# usbspk.net
KiCad netlist of a schematic drawn in EAGLE
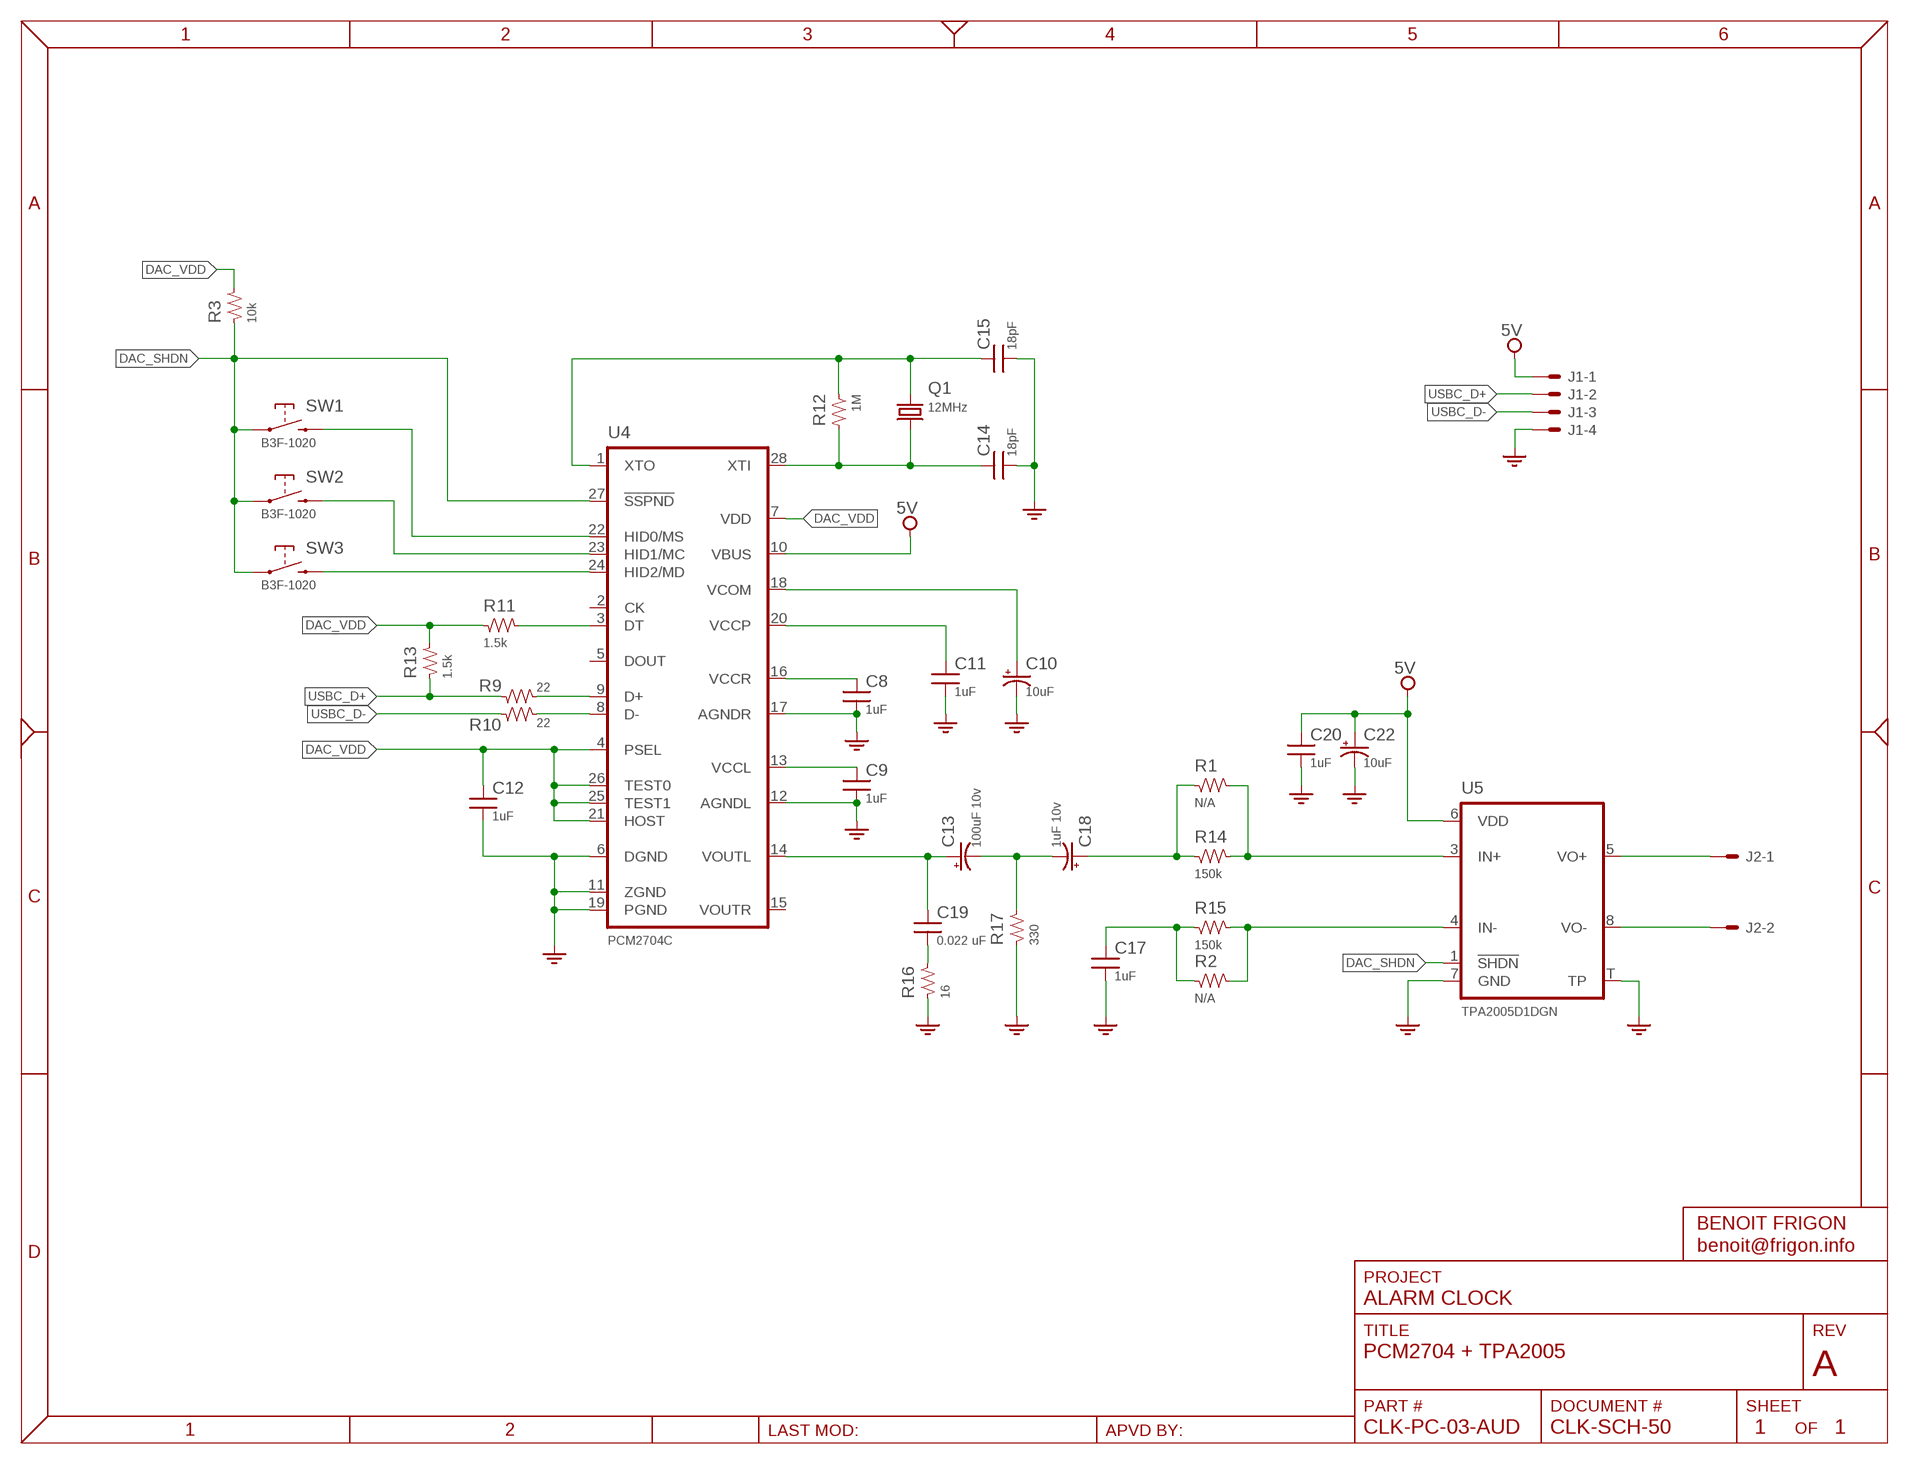
[diagram p0: schematic, sheet 1]

(export (version "E")
  (design (tool "Eeschema 10.0.6"))
  (components
    (comp (ref "C8")
      (value "1uF")
      (footprint "eagle-import:SMD_0603")
      (description "{DESCRIPTION} - SMT 0603 - {value}")
      (fields (field (name "PACKAGE") "SMT 0603"))
      (libsource (lib "eagle-import") (part "CAP-0603"))
    )
    (comp (ref "C9")
      (value "1uF")
      (footprint "eagle-import:SMD_0603")
      (description "{DESCRIPTION} - SMT 0603 - {value}")
      (fields (field (name "PACKAGE") "SMT 0603"))
      (libsource (lib "eagle-import") (part "CAP-0603"))
    )
    (comp (ref "C10")
      (value "10uF")
      (footprint "eagle-import:CAP_S0805")
      (description "{DESCRIPTION} - SMT 0805 - {VALUE}")
      (libsource (lib "eagle-import") (part "CAP-E-S0805"))
    )
    (comp (ref "C11")
      (value "1uF")
      (footprint "eagle-import:SMD_0603")
      (description "{DESCRIPTION} - SMT 0603 - {value}")
      (fields (field (name "PACKAGE") "SMT 0603"))
      (libsource (lib "eagle-import") (part "CAP-0603"))
    )
    (comp (ref "C12")
      (value "1uF")
      (footprint "eagle-import:SMD_0603")
      (libsource (lib "eagle-import") (part "CAP-0603"))
    )
    (comp (ref "C13")
      (value "100uF 10v")
      (footprint "eagle-import:CAP_S1210")
      (libsource (lib "eagle-import") (part "CAP-E-S1210"))
    )
    (comp (ref "C14")
      (value "18pF")
      (footprint "eagle-import:SMD_0603")
      (libsource (lib "eagle-import") (part "CAP-0603"))
    )
    (comp (ref "C15")
      (value "18pF")
      (footprint "eagle-import:SMD_0603")
      (description "{DESCRIPTION} - SMT 0603 - {value}")
      (fields (field (name "PACKAGE") "SMT 0603"))
      (libsource (lib "eagle-import") (part "CAP-0603"))
    )
    (comp (ref "C17")
      (value "1uF")
      (footprint "eagle-import:SMD_0603")
      (libsource (lib "eagle-import") (part "CAP-0603"))
    )
    (comp (ref "C18")
      (value "1uF 10v")
      (footprint "eagle-import:CAP_S0805")
      (libsource (lib "eagle-import") (part "CAP-E-S0805"))
    )
    (comp (ref "C19")
      (value "0.022 uF")
      (footprint "eagle-import:SMD_0603")
      (libsource (lib "eagle-import") (part "CAP-0603"))
    )
    (comp (ref "C20")
      (value "1uF")
      (footprint "eagle-import:SMD_0603")
      (libsource (lib "eagle-import") (part "CAP-0603"))
    )
    (comp (ref "C22")
      (value "10uF")
      (footprint "eagle-import:CAP_S0805")
      (libsource (lib "eagle-import") (part "CAP-E-S0805"))
    )
    (comp (ref "J1")
      (value "SNG-100-HEADER-04-HDR-V")
      (footprint "eagle-import:HDR_M_4")
      (libsource (lib "eagle-import") (part "SNG-100-HEADER-04-HDR-V"))
    )
    (comp (ref "J2")
      (value "SNG-100-HEADER-02-FL-V")
      (footprint "eagle-import:22-23-2021")
      (fields (field (name "MFG") "Molex"))
      (libsource (lib "eagle-import") (part "SNG-100-HEADER-02-FL-V"))
    )
    (comp (ref "Q1")
      (value "12MHz")
      (footprint "eagle-import:HC49_S")
      (fields (field (name "MFG") "TXC") (field (name "PART_NO") "9C-12.000MEEJ-T"))
      (libsource (lib "eagle-import") (part "XTALHC49S"))
    )
    (comp (ref "R1")
      (value "N/A")
      (footprint "eagle-import:SMD_0603")
      (description "{DESCRIPTION} - SMT 0603 - {VALUE}")
      (fields (field (name "PACKAGE") "SMT 0603"))
      (libsource (lib "eagle-import") (part "RES-0603"))
    )
    (comp (ref "R2")
      (value "N/A")
      (footprint "eagle-import:SMD_0603")
      (description "{DESCRIPTION} - SMT 0603 - {VALUE}")
      (fields (field (name "PACKAGE") "SMT 0603"))
      (libsource (lib "eagle-import") (part "RES-0603"))
    )
    (comp (ref "R3")
      (value "10k")
      (footprint "eagle-import:SMD_0603")
      (libsource (lib "eagle-import") (part "RES-0603"))
    )
    (comp (ref "R9")
      (value "22")
      (footprint "eagle-import:SMD_0603")
      (libsource (lib "eagle-import") (part "RES-0603"))
    )
    (comp (ref "R10")
      (value "22")
      (footprint "eagle-import:SMD_0603")
      (libsource (lib "eagle-import") (part "RES-0603"))
    )
    (comp (ref "R11")
      (value "1.5k")
      (footprint "eagle-import:SMD_0603")
      (libsource (lib "eagle-import") (part "RES-0603"))
    )
    (comp (ref "R12")
      (value "1M")
      (footprint "eagle-import:SMD_0603")
      (libsource (lib "eagle-import") (part "RES-0603"))
    )
    (comp (ref "R13")
      (value "1.5k")
      (footprint "eagle-import:SMD_0603")
      (libsource (lib "eagle-import") (part "RES-0603"))
    )
    (comp (ref "R14")
      (value "150k")
      (footprint "eagle-import:SMD_0603")
      (libsource (lib "eagle-import") (part "RES-0603"))
    )
    (comp (ref "R15")
      (value "150k")
      (footprint "eagle-import:SMD_0603")
      (description "{DESCRIPTION} - SMT 0603 - {VALUE}")
      (fields (field (name "PACKAGE") "SMT 0603"))
      (libsource (lib "eagle-import") (part "RES-0603"))
    )
    (comp (ref "R16")
      (value "16")
      (footprint "eagle-import:SMD_0603")
      (libsource (lib "eagle-import") (part "RES-0603"))
    )
    (comp (ref "R17")
      (value "330")
      (footprint "eagle-import:SMD_0603")
      (libsource (lib "eagle-import") (part "RES-0603"))
    )
    (comp (ref "SW1")
      (value "B3F-1020")
      (footprint "eagle-import:B3F-10XX")
      (fields (field (name "MFG") "Omron Electronics"))
      (libsource (lib "eagle-import") (part "B3F-?1020"))
    )
    (comp (ref "SW2")
      (value "B3F-1020")
      (footprint "eagle-import:B3F-10XX")
      (description "{DESCRIPTION} - 6x6mm - 5mm Pitch - 100g")
      (fields (field (name "MFG") "Omron Electronics") (field (name "MFG_1") "Omron Electronics"))
      (libsource (lib "eagle-import") (part "B3F-?1020"))
    )
    (comp (ref "SW3")
      (value "B3F-1020")
      (footprint "eagle-import:B3F-10XX")
      (description "{DESCRIPTION} - 6x6mm - 5mm Pitch - 100g")
      (fields (field (name "MFG") "Omron Electronics") (field (name "MFG_1") "Omron Electronics"))
      (libsource (lib "eagle-import") (part "B3F-?1020"))
    )
    (comp (ref "U4")
      (value "PCM2704C")
      (footprint "eagle-import:TSSOP28")
      (libsource (lib "eagle-import") (part "PCM2704C"))
    )
    (comp (ref "U5")
      (value "TPA2005D1DGN")
      (footprint "eagle-import:PPSOP8")
      (libsource (lib "eagle-import") (part "TPA2005D1?DGN"))
    )
  )
  (nets
    (net (code "1") (name "5V") (class "Default")
      (node (ref "C20") (pin "1") (pinfunction "1_1") (pintype "passive"))
      (node (ref "C22") (pin "+") (pinfunction "+_+") (pintype "passive"))
      (node (ref "J1") (pin "1") (pinfunction "S_1") (pintype "bidirectional"))
      (node (ref "U4") (pin "10") (pinfunction "VBUS_10") (pintype "bidirectional"))
      (node (ref "U5") (pin "6") (pinfunction "VDD_6") (pintype "bidirectional"))
    )
    (net (code "2") (name "DAC_SHDN") (class "Default")
      (node (ref "R3") (pin "1") (pinfunction "1_1") (pintype "passive"))
      (node (ref "SW1") (pin "3") (pinfunction "1_3") (pintype "passive"))
      (node (ref "SW1") (pin "4") (pinfunction "1_4") (pintype "passive"))
      (node (ref "SW2") (pin "3") (pinfunction "1_3") (pintype "passive"))
      (node (ref "SW2") (pin "4") (pinfunction "1_4") (pintype "passive"))
      (node (ref "SW3") (pin "3") (pinfunction "1_3") (pintype "passive"))
      (node (ref "SW3") (pin "4") (pinfunction "1_4") (pintype "passive"))
      (node (ref "U4") (pin "27") (pinfunction "~{SSPND}_27") (pintype "bidirectional"))
      (node (ref "U5") (pin "1") (pinfunction "~{SHDN}_1") (pintype "bidirectional"))
    )
    (net (code "3") (name "DAC_VDD") (class "Default")
      (node (ref "C12") (pin "1") (pinfunction "1_1") (pintype "passive"))
      (node (ref "R11") (pin "1") (pinfunction "1_1") (pintype "passive"))
      (node (ref "R13") (pin "2") (pinfunction "2_2") (pintype "passive"))
      (node (ref "R3") (pin "2") (pinfunction "2_2") (pintype "passive"))
      (node (ref "U4") (pin "21") (pinfunction "HOST_21") (pintype "bidirectional"))
      (node (ref "U4") (pin "25") (pinfunction "TEST1_25") (pintype "bidirectional"))
      (node (ref "U4") (pin "26") (pinfunction "TEST0_26") (pintype "bidirectional"))
      (node (ref "U4") (pin "4") (pinfunction "PSEL_4") (pintype "bidirectional"))
      (node (ref "U4") (pin "7") (pinfunction "VDD_7") (pintype "bidirectional"))
    )
    (net (code "4") (name "GND") (class "Default")
      (node (ref "C10") (pin "-") (pinfunction "-_-") (pintype "passive"))
      (node (ref "C11") (pin "2") (pinfunction "2_2") (pintype "passive"))
      (node (ref "C12") (pin "2") (pinfunction "2_2") (pintype "passive"))
      (node (ref "C14") (pin "2") (pinfunction "2_2") (pintype "passive"))
      (node (ref "C15") (pin "2") (pinfunction "2_2") (pintype "passive"))
      (node (ref "C17") (pin "2") (pinfunction "2_2") (pintype "passive"))
      (node (ref "C20") (pin "2") (pinfunction "2_2") (pintype "passive"))
      (node (ref "C22") (pin "-") (pinfunction "-_-") (pintype "passive"))
      (node (ref "C8") (pin "2") (pinfunction "2_2") (pintype "passive"))
      (node (ref "C9") (pin "2") (pinfunction "2_2") (pintype "passive"))
      (node (ref "J1") (pin "4") (pinfunction "S_4") (pintype "bidirectional"))
      (node (ref "R16") (pin "1") (pinfunction "1_1") (pintype "passive"))
      (node (ref "R17") (pin "1") (pinfunction "1_1") (pintype "passive"))
      (node (ref "U4") (pin "11") (pinfunction "ZGND_11") (pintype "bidirectional"))
      (node (ref "U4") (pin "12") (pinfunction "AGNDL_12") (pintype "bidirectional"))
      (node (ref "U4") (pin "17") (pinfunction "AGNDR_17") (pintype "bidirectional"))
      (node (ref "U4") (pin "19") (pinfunction "PGND_19") (pintype "bidirectional"))
      (node (ref "U4") (pin "6") (pinfunction "DGND_6") (pintype "bidirectional"))
      (node (ref "U5") (pin "7") (pinfunction "GND_7") (pintype "bidirectional"))
      (node (ref "U5") (pin "T") (pinfunction "TP_T") (pintype "bidirectional"))
    )
    (net (code "5") (name "Net-(C13-Pad-)") (class "Default")
      (node (ref "C13") (pin "-") (pinfunction "-_-") (pintype "passive"))
      (node (ref "C18") (pin "-") (pinfunction "-_-") (pintype "passive"))
      (node (ref "R17") (pin "2") (pinfunction "2_2") (pintype "passive"))
    )
    (net (code "6") (name "Net-(C17-Pad1)") (class "Default")
      (node (ref "C17") (pin "1") (pinfunction "1_1") (pintype "passive"))
      (node (ref "R15") (pin "1") (pinfunction "1_1") (pintype "passive"))
      (node (ref "R2") (pin "1") (pinfunction "1_1") (pintype "passive"))
    )
    (net (code "7") (name "Net-(C18-Pad+)") (class "Default")
      (node (ref "C18") (pin "+") (pinfunction "+_+") (pintype "passive"))
      (node (ref "R1") (pin "1") (pinfunction "1_1") (pintype "passive"))
      (node (ref "R14") (pin "1") (pinfunction "1_1") (pintype "passive"))
    )
    (net (code "8") (name "Net-(C19-Pad2)") (class "Default")
      (node (ref "C19") (pin "2") (pinfunction "2_2") (pintype "passive"))
      (node (ref "R16") (pin "2") (pinfunction "2_2") (pintype "passive"))
    )
    (net (code "9") (name "Net-(J2A-S)") (class "Default")
      (node (ref "J2") (pin "1") (pinfunction "S_1") (pintype "bidirectional"))
      (node (ref "U5") (pin "5") (pinfunction "VO+_5") (pintype "bidirectional"))
    )
    (net (code "10") (name "Net-(J2B-S)") (class "Default")
      (node (ref "J2") (pin "2") (pinfunction "S_2") (pintype "bidirectional"))
      (node (ref "U5") (pin "8") (pinfunction "VO-_8") (pintype "bidirectional"))
    )
    (net (code "11") (name "Net-(U4-D+)") (class "Default")
      (node (ref "R9") (pin "2") (pinfunction "2_2") (pintype "passive"))
      (node (ref "U4") (pin "9") (pinfunction "D+_9") (pintype "bidirectional"))
    )
    (net (code "12") (name "Net-(U4-D-)") (class "Default")
      (node (ref "R10") (pin "2") (pinfunction "2_2") (pintype "passive"))
      (node (ref "U4") (pin "8") (pinfunction "D-_8") (pintype "bidirectional"))
    )
    (net (code "13") (name "Net-(U4-DT)") (class "Default")
      (node (ref "R11") (pin "2") (pinfunction "2_2") (pintype "passive"))
      (node (ref "U4") (pin "3") (pinfunction "DT_3") (pintype "bidirectional"))
    )
    (net (code "14") (name "Net-(U4-HID0{slash}MS)") (class "Default")
      (node (ref "SW1") (pin "1") (pinfunction "2_1") (pintype "passive"))
      (node (ref "SW1") (pin "2") (pinfunction "2_2") (pintype "passive"))
      (node (ref "U4") (pin "22") (pinfunction "HID0/MS_22") (pintype "bidirectional"))
    )
    (net (code "15") (name "Net-(U4-HID1{slash}MC)") (class "Default")
      (node (ref "SW2") (pin "1") (pinfunction "2_1") (pintype "passive"))
      (node (ref "SW2") (pin "2") (pinfunction "2_2") (pintype "passive"))
      (node (ref "U4") (pin "23") (pinfunction "HID1/MC_23") (pintype "bidirectional"))
    )
    (net (code "16") (name "Net-(U4-HID2{slash}MD)") (class "Default")
      (node (ref "SW3") (pin "1") (pinfunction "2_1") (pintype "passive"))
      (node (ref "SW3") (pin "2") (pinfunction "2_2") (pintype "passive"))
      (node (ref "U4") (pin "24") (pinfunction "HID2/MD_24") (pintype "bidirectional"))
    )
    (net (code "17") (name "Net-(U4-VCCL)") (class "Default")
      (node (ref "C9") (pin "1") (pinfunction "1_1") (pintype "passive"))
      (node (ref "U4") (pin "13") (pinfunction "VCCL_13") (pintype "bidirectional"))
    )
    (net (code "18") (name "Net-(U4-VCCP)") (class "Default")
      (node (ref "C11") (pin "1") (pinfunction "1_1") (pintype "passive"))
      (node (ref "U4") (pin "20") (pinfunction "VCCP_20") (pintype "bidirectional"))
    )
    (net (code "19") (name "Net-(U4-VCCR)") (class "Default")
      (node (ref "C8") (pin "1") (pinfunction "1_1") (pintype "passive"))
      (node (ref "U4") (pin "16") (pinfunction "VCCR_16") (pintype "bidirectional"))
    )
    (net (code "20") (name "Net-(U4-VCOM)") (class "Default")
      (node (ref "C10") (pin "+") (pinfunction "+_+") (pintype "passive"))
      (node (ref "U4") (pin "18") (pinfunction "VCOM_18") (pintype "bidirectional"))
    )
    (net (code "21") (name "Net-(U4-VOUTL)") (class "Default")
      (node (ref "C13") (pin "+") (pinfunction "+_+") (pintype "passive"))
      (node (ref "C19") (pin "1") (pinfunction "1_1") (pintype "passive"))
      (node (ref "U4") (pin "14") (pinfunction "VOUTL_14") (pintype "bidirectional"))
    )
    (net (code "22") (name "Net-(U4-XTI)") (class "Default")
      (node (ref "C14") (pin "1") (pinfunction "1_1") (pintype "passive"))
      (node (ref "Q1") (pin "2") (pinfunction "2_2") (pintype "passive"))
      (node (ref "R12") (pin "2") (pinfunction "2_2") (pintype "passive"))
      (node (ref "U4") (pin "28") (pinfunction "XTI_28") (pintype "bidirectional"))
    )
    (net (code "23") (name "Net-(U4-XTO)") (class "Default")
      (node (ref "C15") (pin "1") (pinfunction "1_1") (pintype "passive"))
      (node (ref "Q1") (pin "1") (pinfunction "1_1") (pintype "passive"))
      (node (ref "R12") (pin "1") (pinfunction "1_1") (pintype "passive"))
      (node (ref "U4") (pin "1") (pinfunction "XTO_1") (pintype "bidirectional"))
    )
    (net (code "24") (name "Net-(U5-IN+)") (class "Default")
      (node (ref "R1") (pin "2") (pinfunction "2_2") (pintype "passive"))
      (node (ref "R14") (pin "2") (pinfunction "2_2") (pintype "passive"))
      (node (ref "U5") (pin "3") (pinfunction "IN+_3") (pintype "bidirectional"))
    )
    (net (code "25") (name "Net-(U5-IN-)") (class "Default")
      (node (ref "R15") (pin "2") (pinfunction "2_2") (pintype "passive"))
      (node (ref "R2") (pin "2") (pinfunction "2_2") (pintype "passive"))
      (node (ref "U5") (pin "4") (pinfunction "IN-_4") (pintype "bidirectional"))
    )
    (net (code "26") (name "USBC_D+") (class "Default")
      (node (ref "J1") (pin "2") (pinfunction "S_2") (pintype "bidirectional"))
      (node (ref "R13") (pin "1") (pinfunction "1_1") (pintype "passive"))
      (node (ref "R9") (pin "1") (pinfunction "1_1") (pintype "passive"))
    )
    (net (code "27") (name "USBC_D-") (class "Default")
      (node (ref "J1") (pin "3") (pinfunction "S_3") (pintype "bidirectional"))
      (node (ref "R10") (pin "1") (pinfunction "1_1") (pintype "passive"))
    )
    (net (code "28") (name "unconnected-(U4-CK-Pad2)") (class "Default")
      (node (ref "U4") (pin "2") (pinfunction "CK_2") (pintype "bidirectional"))
    )
    (net (code "29") (name "unconnected-(U4-DOUT-Pad5)") (class "Default")
      (node (ref "U4") (pin "5") (pinfunction "DOUT_5") (pintype "bidirectional"))
    )
    (net (code "30") (name "unconnected-(U4-VOUTR-Pad15)") (class "Default")
      (node (ref "U4") (pin "15") (pinfunction "VOUTR_15") (pintype "bidirectional"))
    )
  )
)
